# untitled2sch.net
KiCad netlist of a schematic drawn in EAGLE
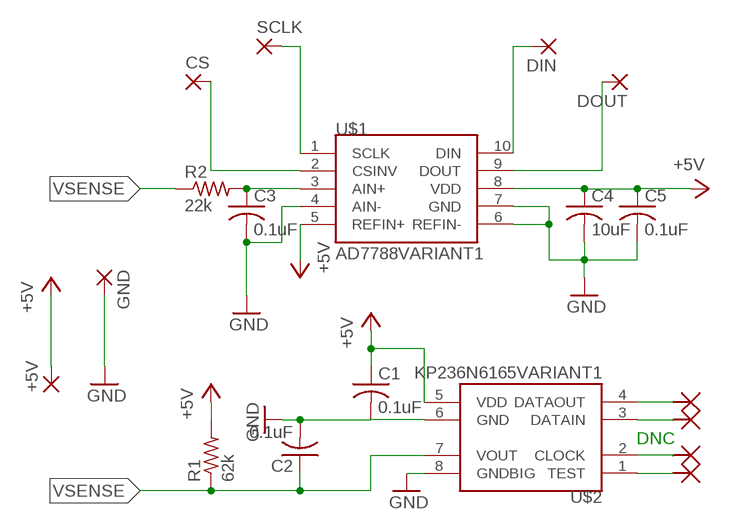
[diagram p0: schematic, sheet 1]

(export (version "E")
  (design (tool "Eeschema 10.0.6"))
  (components
    (comp (ref "+5V")
      (value "WIREPAD1,6/0,8")
      (footprint "eagle-import:1,6_0,8")
      (libsource (lib "eagle-import") (part "WIREPAD1,6/0,8"))
    )
    (comp (ref "C1")
      (value "0.1uF")
      (footprint "eagle-import:C0603K")
      (libsource (lib "eagle-import") (part "C-USC0603K"))
    )
    (comp (ref "C2")
      (value "0.1uF")
      (footprint "eagle-import:C0603K")
      (libsource (lib "eagle-import") (part "C-USC0603K"))
    )
    (comp (ref "C3")
      (value "0.1uF")
      (footprint "eagle-import:C0603K")
      (libsource (lib "eagle-import") (part "C-USC0603K"))
    )
    (comp (ref "C4")
      (value "10uF")
      (footprint "eagle-import:C0603K")
      (libsource (lib "eagle-import") (part "C-USC0603K"))
    )
    (comp (ref "C5")
      (value "0.1uF")
      (footprint "eagle-import:C0603K")
      (libsource (lib "eagle-import") (part "C-USC0603K"))
    )
    (comp (ref "CS")
      (value "WIREPAD1,6/0,8")
      (footprint "eagle-import:1,6_0,8")
      (libsource (lib "eagle-import") (part "WIREPAD1,6/0,8"))
    )
    (comp (ref "DIN")
      (value "WIREPAD1,6/0,8")
      (footprint "eagle-import:1,6_0,8")
      (libsource (lib "eagle-import") (part "WIREPAD1,6/0,8"))
    )
    (comp (ref "DOUT")
      (value "WIREPAD1,6/0,8")
      (footprint "eagle-import:1,6_0,8")
      (libsource (lib "eagle-import") (part "WIREPAD1,6/0,8"))
    )
    (comp (ref "GND")
      (value "WIREPAD1,6/0,8")
      (footprint "eagle-import:1,6_0,8")
      (libsource (lib "eagle-import") (part "WIREPAD1,6/0,8"))
    )
    (comp (ref "R1")
      (value "62k")
      (footprint "eagle-import:R0805")
      (libsource (lib "eagle-import") (part "R-US_R0805"))
    )
    (comp (ref "R2")
      (value "22k")
      (footprint "eagle-import:R0805")
      (libsource (lib "eagle-import") (part "R-US_R0805"))
    )
    (comp (ref "SCLK")
      (value "WIREPAD1,6/0,8")
      (footprint "eagle-import:1,6_0,8")
      (libsource (lib "eagle-import") (part "WIREPAD1,6/0,8"))
    )
    (comp (ref "U$1")
      (value "AD7788VARIANT1")
      (footprint "eagle-import:AD7788")
      (libsource (lib "eagle-import") (part "AD7788VARIANT1"))
    )
    (comp (ref "U$2")
      (value "KP236N6165VARIANT1")
      (footprint "eagle-import:KP236N6165")
      (libsource (lib "eagle-import") (part "KP236N6165VARIANT1"))
    )
  )
  (nets
    (net (code "1") (name "+5V") (class "Default")
      (node (ref "+5V") (pin "1") (pinfunction "P_1") (pintype "passive"))
      (node (ref "C1") (pin "1") (pinfunction "1_1") (pintype "passive"))
      (node (ref "C4") (pin "1") (pinfunction "1_1") (pintype "passive"))
      (node (ref "C5") (pin "1") (pinfunction "1_1") (pintype "passive"))
      (node (ref "R1") (pin "2") (pinfunction "2_2") (pintype "passive"))
      (node (ref "U$1") (pin "5") (pinfunction "REFIN+_5") (pintype "bidirectional"))
      (node (ref "U$1") (pin "8") (pinfunction "VDD_8") (pintype "bidirectional"))
      (node (ref "U$2") (pin "5") (pinfunction "VDD_5") (pintype "bidirectional"))
    )
    (net (code "2") (name "GND") (class "Default")
      (node (ref "C1") (pin "2") (pinfunction "2_2") (pintype "passive"))
      (node (ref "C2") (pin "2") (pinfunction "2_2") (pintype "passive"))
      (node (ref "C3") (pin "2") (pinfunction "2_2") (pintype "passive"))
      (node (ref "C4") (pin "2") (pinfunction "2_2") (pintype "passive"))
      (node (ref "C5") (pin "2") (pinfunction "2_2") (pintype "passive"))
      (node (ref "GND") (pin "1") (pinfunction "P_1") (pintype "passive"))
      (node (ref "U$1") (pin "4") (pinfunction "AIN-_4") (pintype "bidirectional"))
      (node (ref "U$1") (pin "6") (pinfunction "REFIN-_6") (pintype "bidirectional"))
      (node (ref "U$1") (pin "7") (pinfunction "GND_7") (pintype "bidirectional"))
      (node (ref "U$2") (pin "6") (pinfunction "GND_6") (pintype "bidirectional"))
      (node (ref "U$2") (pin "8") (pinfunction "GNDBIG_8") (pintype "bidirectional"))
    )
    (net (code "3") (name "Net-(CS-P)") (class "Default")
      (node (ref "CS") (pin "1") (pinfunction "P_1") (pintype "passive"))
      (node (ref "U$1") (pin "2") (pinfunction "CSINV_2") (pintype "bidirectional"))
    )
    (net (code "4") (name "Net-(DIN-P)") (class "Default")
      (node (ref "DIN") (pin "1") (pinfunction "P_1") (pintype "passive"))
      (node (ref "U$1") (pin "10") (pinfunction "DIN_10") (pintype "bidirectional"))
    )
    (net (code "5") (name "Net-(DOUT-P)") (class "Default")
      (node (ref "DOUT") (pin "1") (pinfunction "P_1") (pintype "passive"))
      (node (ref "U$1") (pin "9") (pinfunction "DOUT_9") (pintype "bidirectional"))
    )
    (net (code "6") (name "Net-(SCLK-P)") (class "Default")
      (node (ref "SCLK") (pin "1") (pinfunction "P_1") (pintype "passive"))
      (node (ref "U$1") (pin "1") (pinfunction "SCLK_1") (pintype "bidirectional"))
    )
    (net (code "7") (name "Net-(U$1-AIN+)") (class "Default")
      (node (ref "C3") (pin "1") (pinfunction "1_1") (pintype "passive"))
      (node (ref "R2") (pin "2") (pinfunction "2_2") (pintype "passive"))
      (node (ref "U$1") (pin "3") (pinfunction "AIN+_3") (pintype "bidirectional"))
    )
    (net (code "8") (name "VSENSE") (class "Default")
      (node (ref "C2") (pin "1") (pinfunction "1_1") (pintype "passive"))
      (node (ref "R1") (pin "1") (pinfunction "1_1") (pintype "passive"))
      (node (ref "R2") (pin "1") (pinfunction "1_1") (pintype "passive"))
      (node (ref "U$2") (pin "7") (pinfunction "VOUT_7") (pintype "bidirectional"))
    )
    (net (code "9") (name "unconnected-(U$2-CLOCK-Pad2)") (class "Default")
      (node (ref "U$2") (pin "2") (pinfunction "CLOCK_2") (pintype "bidirectional"))
    )
    (net (code "10") (name "unconnected-(U$2-DATAIN-Pad3)") (class "Default")
      (node (ref "U$2") (pin "3") (pinfunction "DATAIN_3") (pintype "bidirectional"))
    )
    (net (code "11") (name "unconnected-(U$2-DATAOUT-Pad4)") (class "Default")
      (node (ref "U$2") (pin "4") (pinfunction "DATAOUT_4") (pintype "bidirectional"))
    )
    (net (code "12") (name "unconnected-(U$2-TEST-Pad1)") (class "Default")
      (node (ref "U$2") (pin "1") (pinfunction "TEST_1") (pintype "bidirectional"))
    )
  )
)
